# MakeItHackinDEFCON29Badge_5_withSOIC.net
KiCad netlist of a schematic drawn in EAGLE
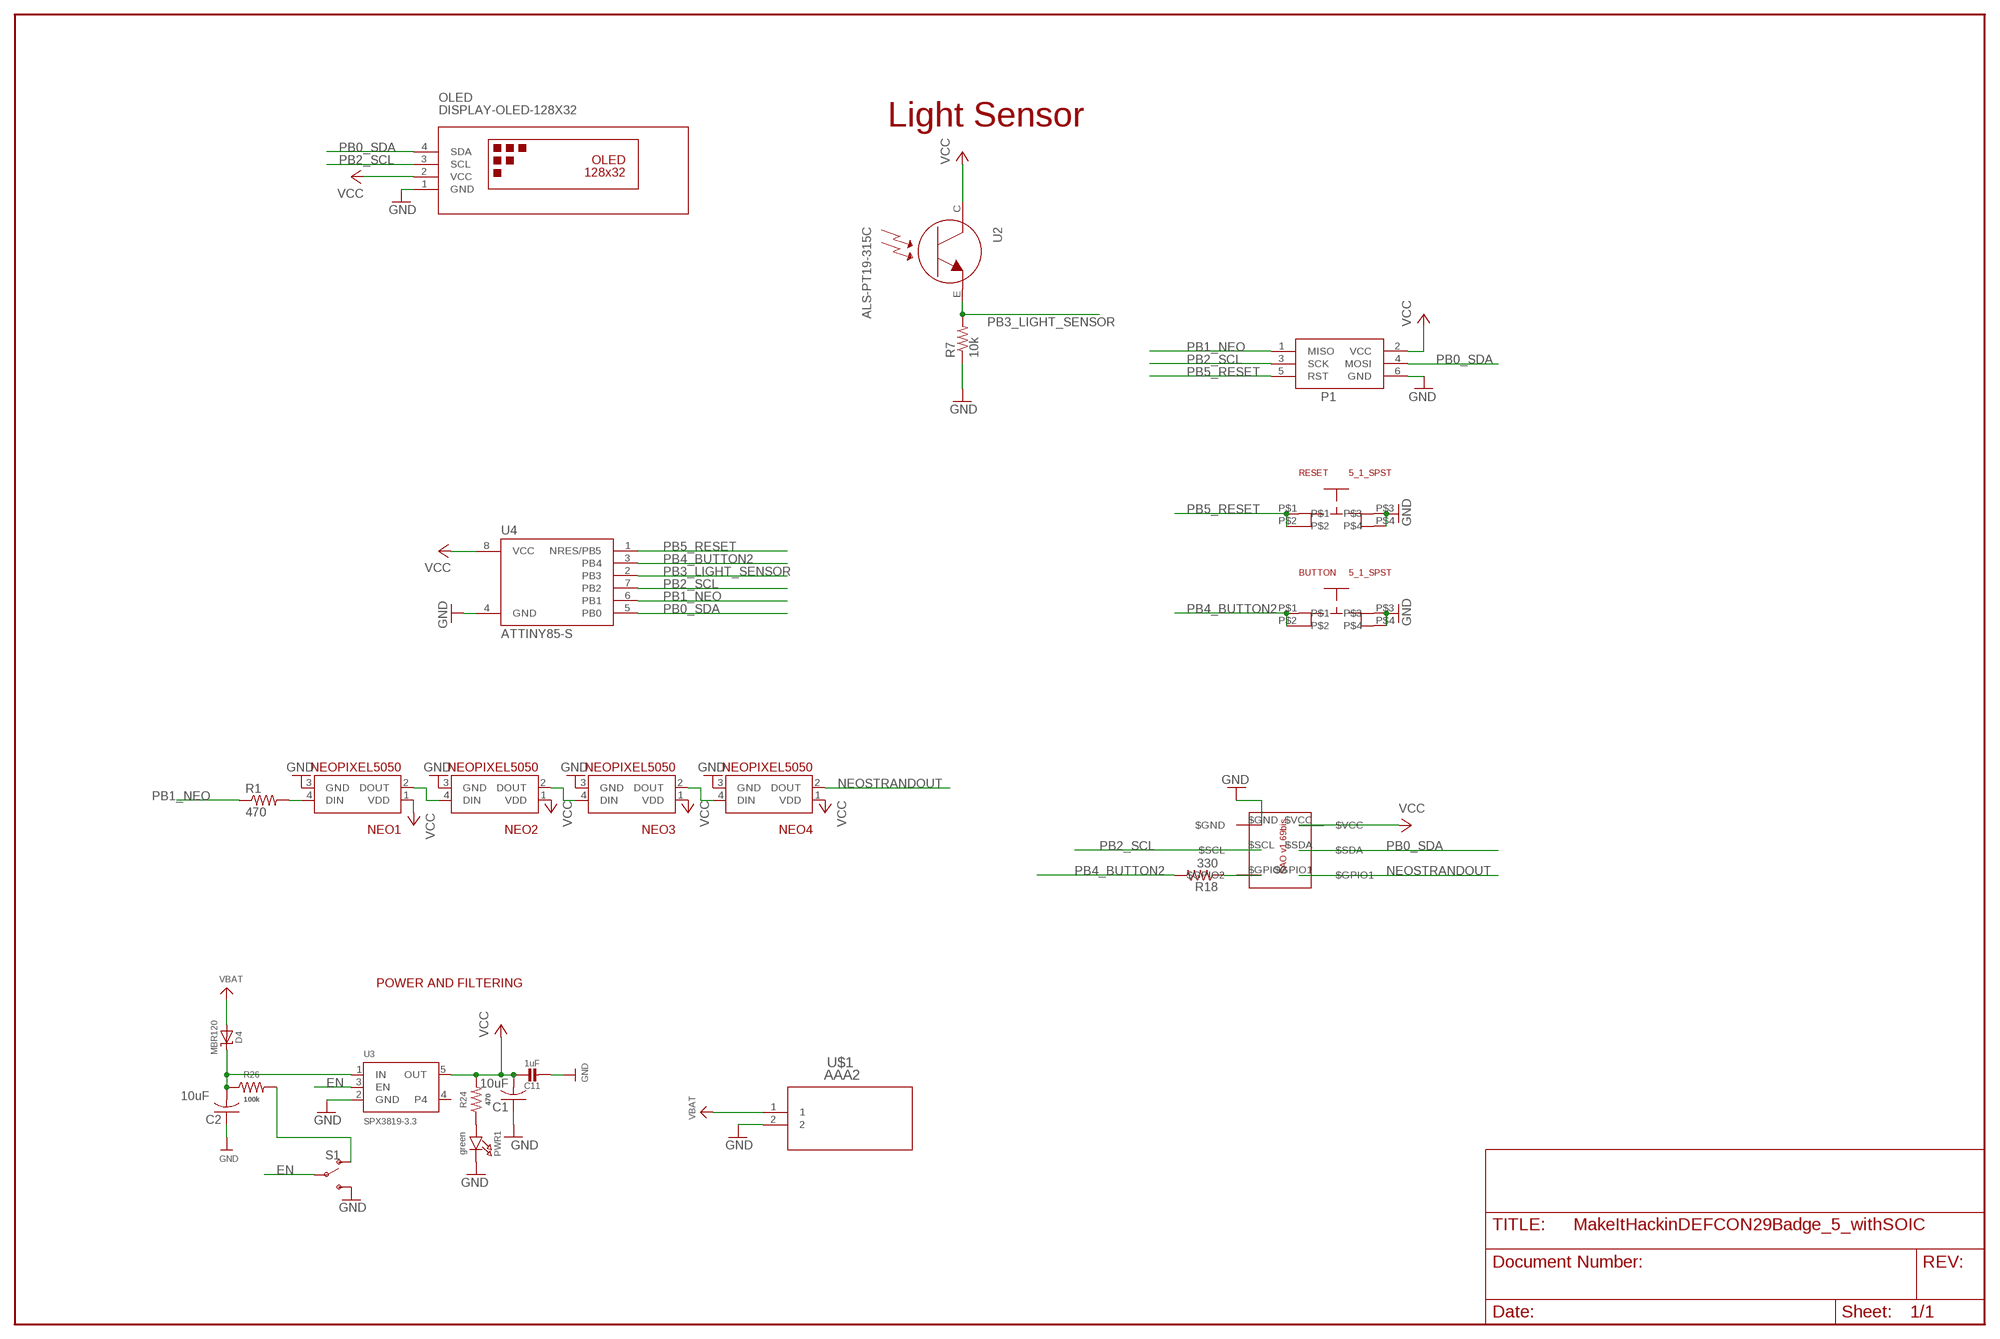
[diagram p0: schematic, sheet 1]

(export (version "E")
  (design (tool "Eeschema 10.0.6"))
  (components
    (comp (ref "BUTTON")
      (value "5_1_SPST")
      (footprint "eagle-import:5_1_SPST")
      (libsource (lib "eagle-import") (part "5_1_SPST"))
    )
    (comp (ref "C1")
      (value "10uF")
      (footprint "eagle-import:C0805")
      (libsource (lib "eagle-import") (part "C-USC0805"))
    )
    (comp (ref "C2")
      (value "10uF")
      (footprint "eagle-import:C0805")
      (libsource (lib "eagle-import") (part "C-USC0805"))
    )
    (comp (ref "C11")
      (value "1uF")
      (footprint "eagle-import:0805-NO@1")
      (libsource (lib "eagle-import") (part "CAP_CERAMIC0805-NOOUTLINE"))
    )
    (comp (ref "D4")
      (value "MBR120")
      (footprint "eagle-import:SOD-123")
      (libsource (lib "eagle-import") (part "DIODE-SCHOTTKYSOD-123"))
    )
    (comp (ref "NEO1")
      (value "NEOPIXEL5050")
      (footprint "eagle-import:NEOPIXEL5050")
      (libsource (lib "eagle-import") (part "NEOPIXEL5050"))
    )
    (comp (ref "NEO2")
      (value "NEOPIXEL5050")
      (footprint "eagle-import:NEOPIXEL5050")
      (libsource (lib "eagle-import") (part "NEOPIXEL5050"))
    )
    (comp (ref "NEO3")
      (value "NEOPIXEL5050")
      (footprint "eagle-import:NEOPIXEL5050")
      (libsource (lib "eagle-import") (part "NEOPIXEL5050"))
    )
    (comp (ref "NEO4")
      (value "NEOPIXEL5050")
      (footprint "eagle-import:NEOPIXEL5050")
      (libsource (lib "eagle-import") (part "NEOPIXEL5050"))
    )
    (comp (ref "OLED")
      (value "DISPLAY-OLED-128X32")
      (footprint "eagle-import:DISPLAY-OLED-128X32")
      (libsource (lib "eagle-import") (part "DISPLAY-OLED-128X32"))
    )
    (comp (ref "P1")
      (value "AVRISP-6")
      (footprint "eagle-import:AVRISP")
      (libsource (lib "eagle-import") (part "AVRISP-6"))
    )
    (comp (ref "PWR1")
      (value "green")
      (footprint "eagle-import:CHIPLED_0805_NOOUTLINE")
      (libsource (lib "eagle-import") (part "LED0805_NOOUTLINE"))
    )
    (comp (ref "R1")
      (value "470")
      (footprint "eagle-import:R0805")
      (libsource (lib "eagle-import") (part "R-US_R0805"))
    )
    (comp (ref "R7")
      (value "10k")
      (footprint "eagle-import:R0805")
      (libsource (lib "eagle-import") (part "R-US_R0805"))
    )
    (comp (ref "R18")
      (value "330")
      (footprint "eagle-import:R0805")
      (libsource (lib "eagle-import") (part "R-US_R0805"))
    )
    (comp (ref "R24")
      (value "470")
      (footprint "eagle-import:R0805")
      (libsource (lib "eagle-import") (part "R-US_R0805"))
    )
    (comp (ref "R26")
      (value "100k")
      (footprint "eagle-import:R0805")
      (libsource (lib "eagle-import") (part "R-US_R0805"))
    )
    (comp (ref "RESET")
      (value "5_1_SPST")
      (footprint "eagle-import:5_1_SPST")
      (libsource (lib "eagle-import") (part "5_1_SPST"))
    )
    (comp (ref "S1")
      (value "SWITCH-SPDT-SMD-AYZ0202")
      (footprint "eagle-import:SWITCH_DPDT_SMD_AYZ0202")
      (libsource (lib "eagle-import") (part "SWITCH-SPDT-SMD-AYZ0202"))
    )
    (comp (ref "U$1")
      (value "AAA2")
      (footprint "eagle-import:AAA2")
      (libsource (lib "eagle-import") (part "AAA2"))
    )
    (comp (ref "U$3")
      (value "SAO-1.69")
      (footprint "eagle-import:2X3-SHROUDED-FEMALE")
      (libsource (lib "eagle-import") (part "SAO-1.69"))
    )
    (comp (ref "U2")
      (value "ALS-PT19-315C")
      (footprint "eagle-import:ALS-PT19-315C")
      (libsource (lib "eagle-import") (part "LIGHT_ALS-PT19-315C"))
    )
    (comp (ref "U3")
      (value "SPX3819-3.3")
      (footprint "eagle-import:SOT23-5")
      (libsource (lib "eagle-import") (part "VREG_SOT23-5"))
    )
    (comp (ref "U4")
      (value "ATTINY85-S")
      (footprint "eagle-import:SOIC8_EIAJ_208MIL")
      (libsource (lib "eagle-import") (part "ATTINY85S-"))
    )
  )
  (nets
    (net (code "1") (name "/EN") (class "Default")
      (node (ref "S1") (pin "2") (pinfunction "P_2") (pintype "passive"))
      (node (ref "U3") (pin "3") (pinfunction "EN_3") (pintype "input"))
    )
    (net (code "2") (name "/NEOSTRANDOUT") (class "Default")
      (node (ref "NEO4") (pin "2") (pinfunction "DOUT_2") (pintype "bidirectional"))
      (node (ref "U$3") (pin "$GPIO1") (pinfunction "$GPIO1_$GPIO1") (pintype "bidirectional"))
    )
    (net (code "3") (name "/PB0_SDA") (class "Default")
      (node (ref "OLED") (pin "4") (pinfunction "SDA_4") (pintype "bidirectional"))
      (node (ref "P1") (pin "4") (pinfunction "MOSI_4") (pintype "output"))
      (node (ref "U$3") (pin "$SDA") (pinfunction "$SDA_$SDA") (pintype "bidirectional"))
      (node (ref "U4") (pin "5") (pinfunction "PB0_5") (pintype "bidirectional"))
    )
    (net (code "4") (name "/PB1_NEO") (class "Default")
      (node (ref "P1") (pin "1") (pinfunction "MISO_1") (pintype "input"))
      (node (ref "R1") (pin "1") (pinfunction "1_1") (pintype "passive"))
      (node (ref "U4") (pin "6") (pinfunction "PB1_6") (pintype "bidirectional"))
    )
    (net (code "5") (name "/PB2_SCL") (class "Default")
      (node (ref "OLED") (pin "3") (pinfunction "SCL_3") (pintype "bidirectional"))
      (node (ref "P1") (pin "3") (pinfunction "SCK_3") (pintype "output"))
      (node (ref "U$3") (pin "$SCL") (pinfunction "$SCL_$SCL") (pintype "bidirectional"))
      (node (ref "U4") (pin "7") (pinfunction "PB2_7") (pintype "bidirectional"))
    )
    (net (code "6") (name "/PB3_LIGHT_SENSOR") (class "Default")
      (node (ref "R7") (pin "2") (pinfunction "2_2") (pintype "passive"))
      (node (ref "U2") (pin "E") (pinfunction "E_E") (pintype "bidirectional"))
      (node (ref "U4") (pin "2") (pinfunction "PB3_2") (pintype "bidirectional"))
    )
    (net (code "7") (name "/PB4_BUTTON2") (class "Default")
      (node (ref "BUTTON") (pin "P$1") (pinfunction "P$1_P$1") (pintype "bidirectional"))
      (node (ref "BUTTON") (pin "P$2") (pinfunction "P$2_P$2") (pintype "bidirectional"))
      (node (ref "R18") (pin "2") (pinfunction "2_2") (pintype "passive"))
      (node (ref "U4") (pin "3") (pinfunction "PB4_3") (pintype "bidirectional"))
    )
    (net (code "8") (name "/PB5_RESET") (class "Default")
      (node (ref "P1") (pin "5") (pinfunction "RST_5") (pintype "output"))
      (node (ref "RESET") (pin "P$1") (pinfunction "P$1_P$1") (pintype "bidirectional"))
      (node (ref "RESET") (pin "P$2") (pinfunction "P$2_P$2") (pintype "bidirectional"))
      (node (ref "U4") (pin "1") (pinfunction "NRES/PB5_1") (pintype "bidirectional"))
    )
    (net (code "9") (name "GND") (class "Default")
      (node (ref "BUTTON") (pin "P$3") (pinfunction "P$3_P$3") (pintype "bidirectional"))
      (node (ref "BUTTON") (pin "P$4") (pinfunction "P$4_P$4") (pintype "bidirectional"))
      (node (ref "C1") (pin "1") (pinfunction "1_1") (pintype "passive"))
      (node (ref "C11") (pin "2") (pinfunction "2_2") (pintype "passive"))
      (node (ref "C2") (pin "1") (pinfunction "1_1") (pintype "passive"))
      (node (ref "NEO1") (pin "3") (pinfunction "GND_3") (pintype "bidirectional"))
      (node (ref "NEO2") (pin "3") (pinfunction "GND_3") (pintype "bidirectional"))
      (node (ref "NEO3") (pin "3") (pinfunction "GND_3") (pintype "bidirectional"))
      (node (ref "NEO4") (pin "3") (pinfunction "GND_3") (pintype "bidirectional"))
      (node (ref "OLED") (pin "1") (pinfunction "GND_1") (pintype "power_in"))
      (node (ref "P1") (pin "6") (pinfunction "GND_6") (pintype "power_in"))
      (node (ref "PWR1") (pin "C") (pinfunction "C_C") (pintype "passive"))
      (node (ref "R7") (pin "1") (pinfunction "1_1") (pintype "passive"))
      (node (ref "RESET") (pin "P$3") (pinfunction "P$3_P$3") (pintype "bidirectional"))
      (node (ref "RESET") (pin "P$4") (pinfunction "P$4_P$4") (pintype "bidirectional"))
      (node (ref "S1") (pin "3") (pinfunction "S_3") (pintype "passive"))
      (node (ref "U$1") (pin "2") (pinfunction "2_2") (pintype "passive"))
      (node (ref "U$3") (pin "$GND") (pinfunction "$GND_$GND") (pintype "bidirectional"))
      (node (ref "U3") (pin "2") (pinfunction "GND_2") (pintype "power_in"))
      (node (ref "U4") (pin "4") (pinfunction "GND_4") (pintype "power_in"))
    )
    (net (code "10") (name "Net-(NEO1-DIN)") (class "Default")
      (node (ref "NEO1") (pin "4") (pinfunction "DIN_4") (pintype "bidirectional"))
      (node (ref "R1") (pin "2") (pinfunction "2_2") (pintype "passive"))
    )
    (net (code "11") (name "Net-(NEO1-DOUT)") (class "Default")
      (node (ref "NEO1") (pin "2") (pinfunction "DOUT_2") (pintype "bidirectional"))
      (node (ref "NEO2") (pin "4") (pinfunction "DIN_4") (pintype "bidirectional"))
    )
    (net (code "12") (name "Net-(NEO2-DOUT)") (class "Default")
      (node (ref "NEO2") (pin "2") (pinfunction "DOUT_2") (pintype "bidirectional"))
      (node (ref "NEO3") (pin "4") (pinfunction "DIN_4") (pintype "bidirectional"))
    )
    (net (code "13") (name "Net-(NEO3-DOUT)") (class "Default")
      (node (ref "NEO3") (pin "2") (pinfunction "DOUT_2") (pintype "bidirectional"))
      (node (ref "NEO4") (pin "4") (pinfunction "DIN_4") (pintype "bidirectional"))
    )
    (net (code "14") (name "Net-(PWR1-PadA)") (class "Default")
      (node (ref "PWR1") (pin "A") (pinfunction "A_A") (pintype "passive"))
      (node (ref "R24") (pin "1") (pinfunction "1_1") (pintype "passive"))
    )
    (net (code "15") (name "Net-(R18-Pad1)") (class "Default")
      (node (ref "R18") (pin "1") (pinfunction "1_1") (pintype "passive"))
      (node (ref "U$3") (pin "$GPIO2") (pinfunction "$GPIO2_$GPIO2") (pintype "bidirectional"))
    )
    (net (code "16") (name "Net-(S1-O)") (class "Default")
      (node (ref "R26") (pin "2") (pinfunction "2_2") (pintype "passive"))
      (node (ref "S1") (pin "1") (pinfunction "O_1") (pintype "passive"))
    )
    (net (code "17") (name "Net-(U3-IN)") (class "Default")
      (node (ref "C2") (pin "2") (pinfunction "2_2") (pintype "passive"))
      (node (ref "D4") (pin "C") (pinfunction "C_C") (pintype "passive"))
      (node (ref "R26") (pin "1") (pinfunction "1_1") (pintype "passive"))
      (node (ref "U3") (pin "1") (pinfunction "IN_1") (pintype "power_in"))
    )
    (net (code "18") (name "VBAT") (class "Default")
      (node (ref "D4") (pin "A") (pinfunction "A_A") (pintype "passive"))
      (node (ref "U$1") (pin "1") (pinfunction "1_1") (pintype "passive"))
    )
    (net (code "19") (name "VCC") (class "Default")
      (node (ref "C1") (pin "2") (pinfunction "2_2") (pintype "passive"))
      (node (ref "C11") (pin "1") (pinfunction "1_1") (pintype "passive"))
      (node (ref "NEO1") (pin "1") (pinfunction "VDD_1") (pintype "bidirectional"))
      (node (ref "NEO2") (pin "1") (pinfunction "VDD_1") (pintype "bidirectional"))
      (node (ref "NEO3") (pin "1") (pinfunction "VDD_1") (pintype "bidirectional"))
      (node (ref "NEO4") (pin "1") (pinfunction "VDD_1") (pintype "bidirectional"))
      (node (ref "OLED") (pin "2") (pinfunction "VCC_2") (pintype "power_in"))
      (node (ref "P1") (pin "2") (pinfunction "VCC_2") (pintype "power_in"))
      (node (ref "R24") (pin "2") (pinfunction "2_2") (pintype "passive"))
      (node (ref "U$3") (pin "$VCC") (pinfunction "$VCC_$VCC") (pintype "bidirectional"))
      (node (ref "U2") (pin "C") (pinfunction "C_C") (pintype "bidirectional"))
      (node (ref "U3") (pin "5") (pinfunction "OUT_5") (pintype "power_in"))
      (node (ref "U4") (pin "8") (pinfunction "VCC_8") (pintype "power_in"))
    )
    (net (code "20") (name "unconnected-(U3-P4-Pad4)") (class "Default")
      (node (ref "U3") (pin "4") (pinfunction "P4_4") (pintype "bidirectional"))
    )
  )
)
